# 03-Led7seg.net
KiCad netlist of a schematic drawn in Altium Designer
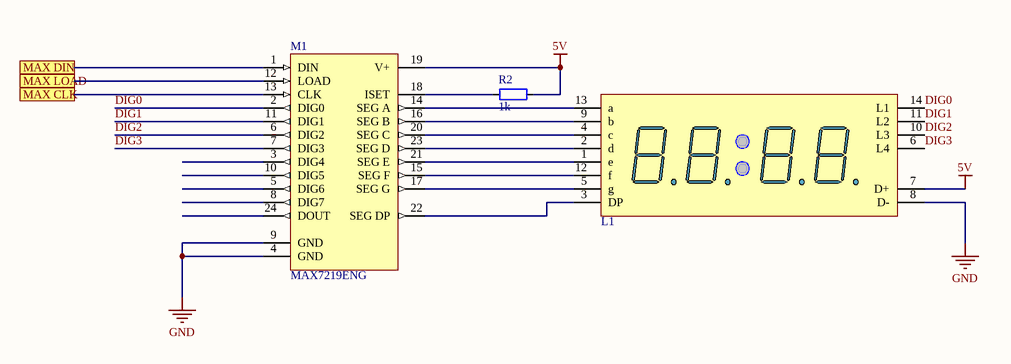
[diagram p0: [03-Led7seg.SchDoc]

(export (version "E")
  (design (tool "Eeschema 10.0.6"))
  (components
    (comp (ref "L1")
      (value "Led 7 Seg 4 digit - Anode")
      (footprint "LED7SEG-4-0.56-RG")
      (libsource (lib "My Library") (part "LED7SEG-4-RG"))
    )
    (comp (ref "M1")
      (value "MAX7219ENG")
      (footprint "DIP24/W0.3")
      (description "Serially Interfaced, 8-Digit LED Display Driver")
      (fields (field (name "PUBLISHER") "Altium Limited"))
      (libsource (lib "My Library") (part "MAX7219ENG"))
    )
    (comp (ref "R2")
      (value "1k")
      (footprint "RES-SMD-0805")
      (description "Resistor")
      (fields
        (field (name "MANUFACTURER") "Generic Components")
        (field (name "PUBLISHER") "Altium Hobart Technology Centre")
      )
      (libsource (lib "My Library") (part "Resistor - SMD"))
    )
  )
  (nets
    (net (code "1") (name "/DIG0") (class "Default")
      (node (ref "L1") (pin "14") (pinfunction "L1_14") (pintype "passive"))
      (node (ref "M1") (pin "2") (pinfunction "DIG0_2") (pintype "output"))
    )
    (net (code "2") (name "/DIG1") (class "Default")
      (node (ref "L1") (pin "11") (pinfunction "L2_11") (pintype "passive"))
      (node (ref "M1") (pin "11") (pinfunction "DIG1_11") (pintype "output"))
    )
    (net (code "3") (name "/DIG2") (class "Default")
      (node (ref "L1") (pin "10") (pinfunction "L3_10") (pintype "passive"))
      (node (ref "M1") (pin "6") (pinfunction "DIG2_6") (pintype "output"))
    )
    (net (code "4") (name "/DIG3") (class "Default")
      (node (ref "L1") (pin "6") (pinfunction "L4_6") (pintype "passive"))
      (node (ref "M1") (pin "7") (pinfunction "DIG3_7") (pintype "output"))
    )
    (net (code "5") (name "/MAX CLK") (class "Default")
      (node (ref "M1") (pin "13") (pinfunction "CLK_13") (pintype "input"))
    )
    (net (code "6") (name "/MAX DIN") (class "Default")
      (node (ref "M1") (pin "1") (pinfunction "DIN_1") (pintype "input"))
    )
    (net (code "7") (name "/MAX LOAD") (class "Default")
      (node (ref "M1") (pin "12") (pinfunction "LOAD_12") (pintype "input"))
    )
    (net (code "8") (name "5V") (class "Default")
      (node (ref "L1") (pin "7") (pinfunction "D+_7") (pintype "passive"))
      (node (ref "M1") (pin "19") (pinfunction "V+_19") (pintype "power_in"))
      (node (ref "R2") (pin "2") (pinfunction "2_2") (pintype "passive"))
    )
    (net (code "9") (name "GND") (class "Default")
      (node (ref "L1") (pin "8") (pinfunction "D-_8") (pintype "passive"))
      (node (ref "M1") (pin "4") (pinfunction "GND_4") (pintype "power_in"))
      (node (ref "M1") (pin "9") (pinfunction "GND_9") (pintype "power_in"))
    )
    (net (code "10") (name "Net-(L1-DP)") (class "Default")
      (node (ref "L1") (pin "3") (pinfunction "DP_3") (pintype "passive"))
      (node (ref "M1") (pin "22") (pinfunction "SEG_DP_22") (pintype "output"))
    )
    (net (code "11") (name "Net-(L1-a)") (class "Default")
      (node (ref "L1") (pin "13") (pinfunction "a_13") (pintype "passive"))
      (node (ref "M1") (pin "14") (pinfunction "SEG_A_14") (pintype "output"))
    )
    (net (code "12") (name "Net-(L1-b)") (class "Default")
      (node (ref "L1") (pin "9") (pinfunction "b_9") (pintype "passive"))
      (node (ref "M1") (pin "16") (pinfunction "SEG_B_16") (pintype "output"))
    )
    (net (code "13") (name "Net-(L1-c)") (class "Default")
      (node (ref "L1") (pin "4") (pinfunction "c_4") (pintype "passive"))
      (node (ref "M1") (pin "20") (pinfunction "SEG_C_20") (pintype "output"))
    )
    (net (code "14") (name "Net-(L1-d)") (class "Default")
      (node (ref "L1") (pin "2") (pinfunction "d_2") (pintype "passive"))
      (node (ref "M1") (pin "23") (pinfunction "SEG_D_23") (pintype "output"))
    )
    (net (code "15") (name "Net-(L1-e)") (class "Default")
      (node (ref "L1") (pin "1") (pinfunction "e_1") (pintype "passive"))
      (node (ref "M1") (pin "21") (pinfunction "SEG_E_21") (pintype "output"))
    )
    (net (code "16") (name "Net-(L1-f)") (class "Default")
      (node (ref "L1") (pin "12") (pinfunction "f_12") (pintype "passive"))
      (node (ref "M1") (pin "15") (pinfunction "SEG_F_15") (pintype "output"))
    )
    (net (code "17") (name "Net-(L1-g)") (class "Default")
      (node (ref "L1") (pin "5") (pinfunction "g_5") (pintype "passive"))
      (node (ref "M1") (pin "17") (pinfunction "SEG_G_17") (pintype "output"))
    )
    (net (code "18") (name "Net-(M1-ISET)") (class "Default")
      (node (ref "M1") (pin "18") (pinfunction "ISET_18") (pintype "passive"))
      (node (ref "R2") (pin "1") (pinfunction "1_1") (pintype "passive"))
    )
    (net (code "19") (name "unconnected-(M1-DIG4-Pad3)") (class "Default")
      (node (ref "M1") (pin "3") (pinfunction "DIG4_3") (pintype "output"))
    )
    (net (code "20") (name "unconnected-(M1-DIG5-Pad10)") (class "Default")
      (node (ref "M1") (pin "10") (pinfunction "DIG5_10") (pintype "output"))
    )
    (net (code "21") (name "unconnected-(M1-DIG6-Pad5)") (class "Default")
      (node (ref "M1") (pin "5") (pinfunction "DIG6_5") (pintype "output"))
    )
    (net (code "22") (name "unconnected-(M1-DIG7-Pad8)") (class "Default")
      (node (ref "M1") (pin "8") (pinfunction "DIG7_8") (pintype "output"))
    )
    (net (code "23") (name "unconnected-(M1-DOUT-Pad24)") (class "Default")
      (node (ref "M1") (pin "24") (pinfunction "DOUT_24") (pintype "output"))
    )
  )
)
